# Filter.net
KiCad netlist of a schematic drawn in Altium Designer
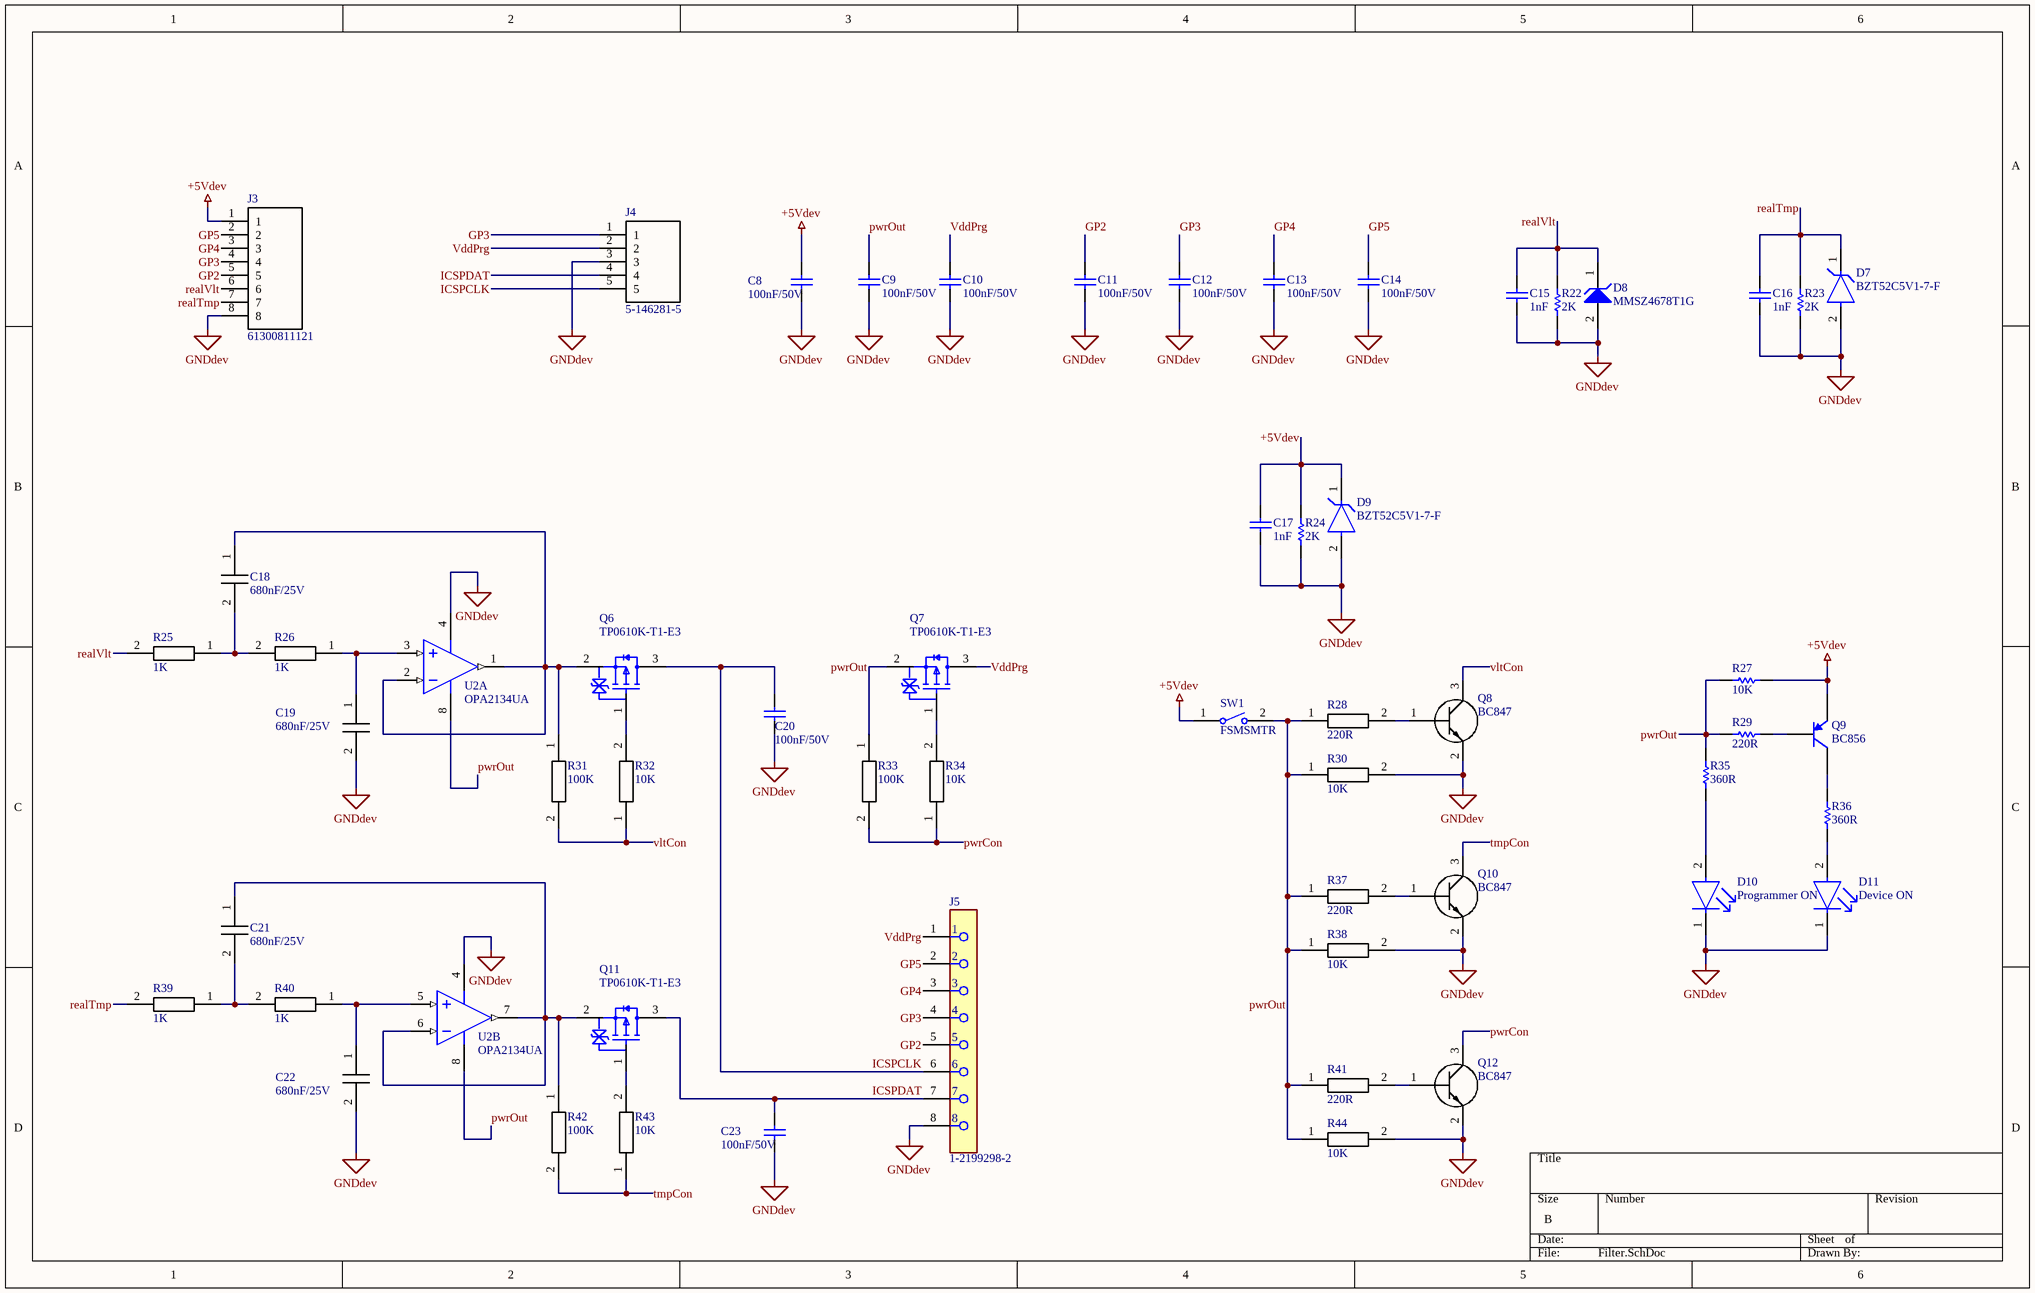
[diagram p0: Filter.SchDoc]

(export (version "E")
  (design (tool "Eeschema 10.0.6"))
  (components
    (comp (ref "C8")
      (value "100nF/50V")
      (footprint "CAPC2013X145X48NL20T23")
      (fields (field (name "MANUFACTURER") "Vitramon") (field (name "PART NUMBER") "VJ0805Y104KNAAT"))
      (libsource (lib "Altium Content Vault") (part "CAP"))
    )
    (comp (ref "C9")
      (value "100nF/50V")
      (footprint "CAPC2013X145X48NL20T23")
      (fields (field (name "MANUFACTURER") "Vitramon") (field (name "PART NUMBER") "VJ0805Y104KNAAT"))
      (libsource (lib "Altium Content Vault") (part "CAP"))
    )
    (comp (ref "C10")
      (value "100nF/50V")
      (footprint "CAPC2013X145X48NL20T23")
      (fields (field (name "MANUFACTURER") "Vitramon") (field (name "PART NUMBER") "VJ0805Y104KNAAT"))
      (libsource (lib "Altium Content Vault") (part "CAP"))
    )
    (comp (ref "C11")
      (value "100nF/50V")
      (footprint "CAPC2013X145X48NL20T23")
      (fields (field (name "MANUFACTURER") "Vitramon") (field (name "PART NUMBER") "VJ0805Y104KNAAT"))
      (libsource (lib "Altium Content Vault") (part "CAP"))
    )
    (comp (ref "C12")
      (value "100nF/50V")
      (footprint "CAPC2013X145X48NL20T23")
      (fields (field (name "MANUFACTURER") "Vitramon") (field (name "PART NUMBER") "VJ0805Y104KNAAT"))
      (libsource (lib "Altium Content Vault") (part "CAP"))
    )
    (comp (ref "C13")
      (value "100nF/50V")
      (footprint "CAPC2013X145X48NL20T23")
      (fields (field (name "MANUFACTURER") "Vitramon") (field (name "PART NUMBER") "VJ0805Y104KNAAT"))
      (libsource (lib "Altium Content Vault") (part "CAP"))
    )
    (comp (ref "C14")
      (value "100nF/50V")
      (footprint "CAPC2013X145X48NL20T23")
      (fields (field (name "MANUFACTURER") "Vitramon") (field (name "PART NUMBER") "VJ0805Y104KNAAT"))
      (libsource (lib "Altium Content Vault") (part "CAP"))
    )
    (comp (ref "C15")
      (value "1nF")
      (footprint "CAPC2013X145X48ML20T23")
      (fields (field (name "PART NUMBER") "VJ0805Y102KXAMC") (field (name "MANUFACTURER") "Vitramon"))
      (libsource (lib "Altium Content Vault") (part "CAP"))
    )
    (comp (ref "C16")
      (value "1nF")
      (footprint "CAPC2013X145X48ML20T23")
      (fields (field (name "PART NUMBER") "VJ0805Y102KXAMC") (field (name "MANUFACTURER") "Vitramon"))
      (libsource (lib "Altium Content Vault") (part "CAP"))
    )
    (comp (ref "C17")
      (value "1nF")
      (footprint "CAPC2013X145X48ML20T23")
      (fields (field (name "PART NUMBER") "VJ0805Y102KXAMC") (field (name "MANUFACTURER") "Vitramon"))
      (libsource (lib "Altium Content Vault") (part "CAP"))
    )
    (comp (ref "C18")
      (value "680nF/25V")
      (footprint "SamacSys:CAPC2012X95N")
      (description "Capacitor")
      (fields (field (name "MANUFACTURER_PART_NUMBER") "GRM219B31E684KA88D"))
      (libsource (lib "*") (part "GRM219B31E684KA88D"))
    )
    (comp (ref "C19")
      (value "680nF/25V")
      (footprint "SamacSys:CAPC2012X95N")
      (description "Capacitor")
      (fields (field (name "MANUFACTURER_PART_NUMBER") "GRM219B31E684KA88D"))
      (libsource (lib "*") (part "GRM219B31E684KA88D"))
    )
    (comp (ref "C20")
      (value "100nF/50V")
      (footprint "CAPC2013X145X48NL20T23")
      (fields (field (name "MANUFACTURER") "Vitramon") (field (name "PART NUMBER") "VJ0805Y104KNAAT"))
      (libsource (lib "Altium Content Vault") (part "CAP"))
    )
    (comp (ref "C21")
      (value "680nF/25V")
      (footprint "SamacSys:CAPC2012X95N")
      (description "Capacitor")
      (fields (field (name "MANUFACTURER_PART_NUMBER") "GRM219B31E684KA88D"))
      (libsource (lib "*") (part "GRM219B31E684KA88D"))
    )
    (comp (ref "C22")
      (value "680nF/25V")
      (footprint "SamacSys:CAPC2012X95N")
      (description "Capacitor")
      (fields (field (name "MANUFACTURER_PART_NUMBER") "GRM219B31E684KA88D"))
      (libsource (lib "*") (part "GRM219B31E684KA88D"))
    )
    (comp (ref "C23")
      (value "100nF/50V")
      (footprint "CAPC2013X145X48NL20T23")
      (fields (field (name "MANUFACTURER") "Vitramon") (field (name "PART NUMBER") "VJ0805Y104KNAAT"))
      (libsource (lib "Altium Content Vault") (part "CAP"))
    )
    (comp (ref "D7")
      (value "BZT52C5V1-7-F")
      (footprint "FP-SOD123-MFG")
      (description "DIODE ZENER 5.1V 500MW SOD123")
      (fields
        (field (name "OCTOPART") "https://octopart.com/bzt52c5v1-7-f-diodes+inc.-326718")
        (field (name "MANUFACTURER") "Diodes Incorporated")
      )
      (libsource (lib "Altium Content Vault") (part "f813f71cba58e380607f5dd3caf9714"))
    )
    (comp (ref "D8")
      (value "MMSZ4678T1G")
      (footprint "ONSC-SOD-123-2-425-04_V")
      (description "Zener Voltage Regulator, 500 mW, 2-Pin SOD-123, Pb-Free, Tape and Reel")
      (fields (field (name "MANUFACTURER") "On Semiconductor"))
      (libsource (lib "Altium Content Vault") (part "ONSC-K1A2-2"))
    )
    (comp (ref "D9")
      (value "BZT52C5V1-7-F")
      (footprint "FP-SOD123-MFG")
      (description "DIODE ZENER 5.1V 500MW SOD123")
      (fields
        (field (name "OCTOPART") "https://octopart.com/bzt52c5v1-7-f-diodes+inc.-326718")
        (field (name "MANUFACTURER") "Diodes Incorporated")
      )
      (libsource (lib "Altium Content Vault") (part "f813f71cba58e380607f5dd3caf9714"))
    )
    (comp (ref "D10")
      (value "Programmer ON")
      (footprint "FP-LG_R971-MFG")
      (description "LED GREEN DIFFUSED 0805 SMD")
      (libsource (lib "Altium Content Vault") (part "8706943c75ba83719d021d2fdc84c58"))
    )
    (comp (ref "D11")
      (value "Device ON")
      (footprint "FP-LS_R976-MFG")
      (description "LED RED DIFFUSED 0805 SMD")
      (libsource (lib "Altium Content Vault") (part "8706943c75ba83719d021d2fdc84c58"))
    )
    (comp (ref "J3")
      (value "61300811121")
      (footprint "SamacSys:HDRV8W64P0X254_1X8_2032X254X854P")
      (description "Connector")
      (fields (field (name "MOUSER PART NUMBER") "710-61300811121"))
      (libsource (lib "*") (part "61300811121"))
    )
    (comp (ref "J4")
      (value "5-146281-5")
      (footprint "SamacSys:HDRV5W67P0X254_1X5_1229X234X821P")
      (description "Connector")
      (fields (field (name "MOUSER PART NUMBER") "571-5-146281-5"))
      (libsource (lib "*") (part "5-146281-5"))
    )
    (comp (ref "J5")
      (value "1-2199298-2")
      (footprint "FP-1-2199298-2-MFG")
      (description "CONN IC DIP SOCKET 8POS TIN")
      (libsource (lib "Altium Content Vault") (part "b0a0b555dd3abf3683e7c330df25cc4"))
    )
    (comp (ref "Q6")
      (value "TP0610K-T1-E3")
      (footprint "FP-S-03946-MFG")
      (description "MOSFET P-CH 60V 185MA SOT23-3")
      (fields
        (field (name "MANUFACTURER") "Vishay")
        (field (name "OCTOPART") "https://octopart.com/tp0610k-t1-e3-vishay-40944172")
      )
      (libsource (lib "Altium Content Vault") (part "bc9d61678d3f6143cc1ffb3a369bd6c"))
    )
    (comp (ref "Q7")
      (value "TP0610K-T1-E3")
      (footprint "FP-S-03946-MFG")
      (description "MOSFET P-CH 60V 185MA SOT23-3")
      (fields
        (field (name "MANUFACTURER") "Vishay")
        (field (name "OCTOPART") "https://octopart.com/tp0610k-t1-e3-vishay-40944172")
      )
      (libsource (lib "Altium Content Vault") (part "bc9d61678d3f6143cc1ffb3a369bd6c"))
    )
    (comp (ref "Q8")
      (value "BC847")
      (footprint "SamacSys:BC847215")
      (description "Transistor BJT NPN")
      (fields
        (field (name "MANUFACTURER_PART_NUMBER") "BC847,215")
        (field (name "MOUSER PART NUMBER") "771-BC847215")
      )
      (libsource (lib "*") (part "BC847,215"))
    )
    (comp (ref "Q9")
      (value "BC856")
      (footprint "NXP-SOT23-3_V")
      (description "PNP General Purpose Transistor, 65 V, -65 to 150 degC, 3-Pin SOT23, RoHS")
      (fields (field (name "MANUFACTURER") "NXP"))
      (libsource (lib "Altium Content Vault") (part "BJT-PNP-BEC-3"))
    )
    (comp (ref "Q10")
      (value "BC847")
      (footprint "SamacSys:BC847215")
      (description "Transistor BJT NPN")
      (fields
        (field (name "MANUFACTURER_PART_NUMBER") "BC847,215")
        (field (name "MOUSER PART NUMBER") "771-BC847215")
      )
      (libsource (lib "*") (part "BC847,215"))
    )
    (comp (ref "Q11")
      (value "TP0610K-T1-E3")
      (footprint "FP-S-03946-MFG")
      (description "MOSFET P-CH 60V 185MA SOT23-3")
      (fields
        (field (name "MANUFACTURER") "Vishay")
        (field (name "OCTOPART") "https://octopart.com/tp0610k-t1-e3-vishay-40944172")
      )
      (libsource (lib "Altium Content Vault") (part "bc9d61678d3f6143cc1ffb3a369bd6c"))
    )
    (comp (ref "Q12")
      (value "BC847")
      (footprint "SamacSys:BC847215")
      (description "Transistor BJT NPN")
      (fields
        (field (name "MANUFACTURER_PART_NUMBER") "BC847,215")
        (field (name "MOUSER PART NUMBER") "771-BC847215")
      )
      (libsource (lib "*") (part "BC847,215"))
    )
    (comp (ref "R22")
      (value "2K")
      (footprint "RESC2013X55X40NL15T20")
      (fields (field (name "MANUFACTURER") "Vishay Dale") (field (name "PART NUMBER") "TNPW08052K00BEEN"))
      (libsource (lib "Altium Content Vault") (part "RES"))
    )
    (comp (ref "R23")
      (value "2K")
      (footprint "RESC2013X55X40NL15T20")
      (fields (field (name "MANUFACTURER") "Vishay Dale") (field (name "PART NUMBER") "TNPW08052K00BEEN"))
      (libsource (lib "Altium Content Vault") (part "RES"))
    )
    (comp (ref "R24")
      (value "2K")
      (footprint "RESC2013X55X40NL15T20")
      (fields (field (name "MANUFACTURER") "Vishay Dale") (field (name "PART NUMBER") "TNPW08052K00BEEN"))
      (libsource (lib "Altium Content Vault") (part "RES"))
    )
    (comp (ref "R25")
      (value "1K")
      (footprint "SamacSys:RESC2012X65N")
      (description "Resistor")
      (fields
        (field (name "MANUFACTURER_PART_NUMBER") "CPF0805B360RE1")
        (field (name "MOUSER PART NUMBER") "279-CPF0805B360RE1")
      )
      (libsource (lib "*") (part "CPF0805B360RE1"))
    )
    (comp (ref "R26")
      (value "1K")
      (footprint "SamacSys:RESC2012X65N")
      (description "Resistor")
      (fields
        (field (name "MANUFACTURER_PART_NUMBER") "CPF0805B360RE1")
        (field (name "MOUSER PART NUMBER") "279-CPF0805B360RE1")
      )
      (libsource (lib "*") (part "CPF0805B360RE1"))
    )
    (comp (ref "R27")
      (value "10K")
      (footprint "RESC2013X55X40NL15T20")
      (fields (field (name "MANUFACTURER") "Vishay Dale") (field (name "PART NUMBER") "TNPW08052K00BEEN"))
      (libsource (lib "Altium Content Vault") (part "RES"))
    )
    (comp (ref "R28")
      (value "220R")
      (footprint "SamacSys:RESC2012X65N")
      (description "Resistor")
      (fields (field (name "MANUFACTURER_PART_NUMBER") "CPF0805B220RE"))
      (libsource (lib "*") (part "CPF0805B220RE"))
    )
    (comp (ref "R29")
      (value "220R")
      (footprint "RESC2013X55X40NL15T20")
      (fields (field (name "MANUFACTURER") "Vishay Dale") (field (name "PART NUMBER") "TNPW08052K00BEEN"))
      (libsource (lib "Altium Content Vault") (part "RES"))
    )
    (comp (ref "R30")
      (value "10K")
      (footprint "SamacSys:RESC2012X65N")
      (description "Resistor")
      (fields (field (name "MANUFACTURER_PART_NUMBER") "CPF0805B220RE"))
      (libsource (lib "*") (part "CPF0805B220RE"))
    )
    (comp (ref "R31")
      (value "100K")
      (footprint "SamacSys:RESC2012X65N")
      (description "Resistor")
      (fields
        (field (name "MANUFACTURER_PART_NUMBER") "CPF0805B360RE1")
        (field (name "MOUSER PART NUMBER") "279-CPF0805B360RE1")
      )
      (libsource (lib "*") (part "CPF0805B360RE1"))
    )
    (comp (ref "R32")
      (value "10K")
      (footprint "SamacSys:RESC2012X65N")
      (description "Resistor")
      (fields
        (field (name "MANUFACTURER_PART_NUMBER") "CPF0805B360RE1")
        (field (name "MOUSER PART NUMBER") "279-CPF0805B360RE1")
      )
      (libsource (lib "*") (part "CPF0805B360RE1"))
    )
    (comp (ref "R33")
      (value "100K")
      (footprint "SamacSys:RESC2012X65N")
      (description "Resistor")
      (fields
        (field (name "MANUFACTURER_PART_NUMBER") "CPF0805B360RE1")
        (field (name "MOUSER PART NUMBER") "279-CPF0805B360RE1")
      )
      (libsource (lib "*") (part "CPF0805B360RE1"))
    )
    (comp (ref "R34")
      (value "10K")
      (footprint "SamacSys:RESC2012X65N")
      (description "Resistor")
      (fields
        (field (name "MANUFACTURER_PART_NUMBER") "CPF0805B360RE1")
        (field (name "MOUSER PART NUMBER") "279-CPF0805B360RE1")
      )
      (libsource (lib "*") (part "CPF0805B360RE1"))
    )
    (comp (ref "R35")
      (value "360R")
      (footprint "RESC2013X55X40NL15T20")
      (fields (field (name "MANUFACTURER") "Vishay Dale") (field (name "PART NUMBER") "TNPW08052K00BEEN"))
      (libsource (lib "Altium Content Vault") (part "RES"))
    )
    (comp (ref "R36")
      (value "360R")
      (footprint "RESC2013X55X40NL15T20")
      (fields (field (name "MANUFACTURER") "Vishay Dale") (field (name "PART NUMBER") "TNPW08052K00BEEN"))
      (libsource (lib "Altium Content Vault") (part "RES"))
    )
    (comp (ref "R37")
      (value "220R")
      (footprint "SamacSys:RESC2012X65N")
      (description "Resistor")
      (fields (field (name "MANUFACTURER_PART_NUMBER") "CPF0805B220RE"))
      (libsource (lib "*") (part "CPF0805B220RE"))
    )
    (comp (ref "R38")
      (value "10K")
      (footprint "SamacSys:RESC2012X65N")
      (description "Resistor")
      (fields (field (name "MANUFACTURER_PART_NUMBER") "CPF0805B220RE"))
      (libsource (lib "*") (part "CPF0805B220RE"))
    )
    (comp (ref "R39")
      (value "1K")
      (footprint "SamacSys:RESC2012X65N")
      (description "Resistor")
      (fields
        (field (name "MANUFACTURER_PART_NUMBER") "CPF0805B360RE1")
        (field (name "MOUSER PART NUMBER") "279-CPF0805B360RE1")
      )
      (libsource (lib "*") (part "CPF0805B360RE1"))
    )
    (comp (ref "R40")
      (value "1K")
      (footprint "SamacSys:RESC2012X65N")
      (description "Resistor")
      (fields
        (field (name "MANUFACTURER_PART_NUMBER") "CPF0805B360RE1")
        (field (name "MOUSER PART NUMBER") "279-CPF0805B360RE1")
      )
      (libsource (lib "*") (part "CPF0805B360RE1"))
    )
    (comp (ref "R41")
      (value "220R")
      (footprint "SamacSys:RESC2012X65N")
      (description "Resistor")
      (fields (field (name "MANUFACTURER_PART_NUMBER") "CPF0805B220RE"))
      (libsource (lib "*") (part "CPF0805B220RE"))
    )
    (comp (ref "R42")
      (value "100K")
      (footprint "SamacSys:RESC2012X65N")
      (description "Resistor")
      (fields
        (field (name "MANUFACTURER_PART_NUMBER") "CPF0805B360RE1")
        (field (name "MOUSER PART NUMBER") "279-CPF0805B360RE1")
      )
      (libsource (lib "*") (part "CPF0805B360RE1"))
    )
    (comp (ref "R43")
      (value "10K")
      (footprint "SamacSys:RESC2012X65N")
      (description "Resistor")
      (fields
        (field (name "MANUFACTURER_PART_NUMBER") "CPF0805B360RE1")
        (field (name "MOUSER PART NUMBER") "279-CPF0805B360RE1")
      )
      (libsource (lib "*") (part "CPF0805B360RE1"))
    )
    (comp (ref "R44")
      (value "10K")
      (footprint "SamacSys:RESC2012X65N")
      (description "Resistor")
      (fields (field (name "MANUFACTURER_PART_NUMBER") "CPF0805B220RE"))
      (libsource (lib "*") (part "CPF0805B220RE"))
    )
    (comp (ref "SW1")
      (value "FSMSMTR")
      (footprint "TECO-FSMSMTR_V")
      (description "FSMSM Push Button Switch, 50 mA, -35 to 85 degC, 2-Pin SMD, RoHS, Tape and Reel")
      (fields (field (name "MANUFACTURER") "TE Connectivity"))
      (libsource (lib "Altium Content Vault") (part "SW-SPST-2_C"))
    )
    (comp (ref "U2")
      (value "OPA2134UA")
      (footprint "D0008A_L")
      (fields (field (name "MANUFACTURER") "Texas Instruments"))
      (libsource (lib "Altium Content Vault") (part "TI-OPA2134D8"))
    )
  )
  (nets
    (net (code "1") (name "+5Vdev") (class "Default")
      (node (ref "C17") (pin "2") (pinfunction "2_2") (pintype "passive"))
      (node (ref "C8") (pin "2") (pinfunction "2_2") (pintype "passive"))
      (node (ref "D9") (pin "1") (pinfunction "C_1") (pintype "passive"))
      (node (ref "J3") (pin "1") (pinfunction "1_1") (pintype "passive"))
      (node (ref "Q9") (pin "2") (pinfunction "E_2") (pintype "passive"))
      (node (ref "R24") (pin "2") (pinfunction "2_2") (pintype "passive"))
      (node (ref "R27") (pin "1") (pinfunction "1_1") (pintype "passive"))
      (node (ref "SW1") (pin "1") (pinfunction "1_1") (pintype "passive"))
    )
    (net (code "2") (name "/GP2") (class "Default")
      (node (ref "C11") (pin "1") (pinfunction "1_1") (pintype "passive"))
      (node (ref "J3") (pin "5") (pinfunction "5_5") (pintype "passive"))
      (node (ref "J5") (pin "5") (pinfunction "5_5") (pintype "passive"))
    )
    (net (code "3") (name "/GP3") (class "Default")
      (node (ref "C12") (pin "1") (pinfunction "1_1") (pintype "passive"))
      (node (ref "J3") (pin "4") (pinfunction "4_4") (pintype "passive"))
      (node (ref "J4") (pin "1") (pinfunction "1_1") (pintype "passive"))
      (node (ref "J5") (pin "4") (pinfunction "4_4") (pintype "passive"))
    )
    (net (code "4") (name "/GP4") (class "Default")
      (node (ref "C13") (pin "1") (pinfunction "1_1") (pintype "passive"))
      (node (ref "J3") (pin "3") (pinfunction "3_3") (pintype "passive"))
      (node (ref "J5") (pin "3") (pinfunction "3_3") (pintype "passive"))
    )
    (net (code "5") (name "/GP5") (class "Default")
      (node (ref "C14") (pin "1") (pinfunction "1_1") (pintype "passive"))
      (node (ref "J3") (pin "2") (pinfunction "2_2") (pintype "passive"))
      (node (ref "J5") (pin "2") (pinfunction "2_2") (pintype "passive"))
    )
    (net (code "6") (name "/ICSPCLK") (class "Default")
      (node (ref "C20") (pin "2") (pinfunction "2_2") (pintype "passive"))
      (node (ref "J4") (pin "5") (pinfunction "5_5") (pintype "passive"))
      (node (ref "J5") (pin "6") (pinfunction "6_6") (pintype "passive"))
      (node (ref "Q6") (pin "3") (pinfunction "D_3") (pintype "passive"))
    )
    (net (code "7") (name "/ICSPDAT") (class "Default")
      (node (ref "C23") (pin "2") (pinfunction "2_2") (pintype "passive"))
      (node (ref "J4") (pin "4") (pinfunction "4_4") (pintype "passive"))
      (node (ref "J5") (pin "7") (pinfunction "7_7") (pintype "passive"))
      (node (ref "Q11") (pin "3") (pinfunction "D_3") (pintype "passive"))
    )
    (net (code "8") (name "/VddPrg") (class "Default")
      (node (ref "C10") (pin "1") (pinfunction "1_1") (pintype "passive"))
      (node (ref "J4") (pin "2") (pinfunction "2_2") (pintype "passive"))
      (node (ref "J5") (pin "1") (pinfunction "1_1") (pintype "passive"))
      (node (ref "Q7") (pin "3") (pinfunction "D_3") (pintype "passive"))
    )
    (net (code "9") (name "/pwrCon") (class "Default")
      (node (ref "Q12") (pin "3") (pinfunction "C_3") (pintype "passive"))
      (node (ref "R33") (pin "2") (pinfunction "2_2") (pintype "passive"))
      (node (ref "R34") (pin "1") (pinfunction "1_1") (pintype "passive"))
    )
    (net (code "10") (name "/pwrOut") (class "Default")
      (node (ref "C9") (pin "1") (pinfunction "1_1") (pintype "passive"))
      (node (ref "Q7") (pin "2") (pinfunction "S_2") (pintype "passive"))
      (node (ref "R27") (pin "2") (pinfunction "2_2") (pintype "passive"))
      (node (ref "R28") (pin "1") (pinfunction "1_1") (pintype "passive"))
      (node (ref "R29") (pin "2") (pinfunction "2_2") (pintype "passive"))
      (node (ref "R30") (pin "1") (pinfunction "1_1") (pintype "passive"))
      (node (ref "R33") (pin "1") (pinfunction "1_1") (pintype "passive"))
      (node (ref "R35") (pin "2") (pinfunction "2_2") (pintype "passive"))
      (node (ref "R37") (pin "1") (pinfunction "1_1") (pintype "passive"))
      (node (ref "R38") (pin "1") (pinfunction "1_1") (pintype "passive"))
      (node (ref "R41") (pin "1") (pinfunction "1_1") (pintype "passive"))
      (node (ref "R44") (pin "1") (pinfunction "1_1") (pintype "passive"))
      (node (ref "SW1") (pin "2") (pinfunction "2_2") (pintype "passive"))
      (node (ref "U2") (pin "8") (pinfunction "V+_8") (pintype "power_in"))
    )
    (net (code "11") (name "/realTmp") (class "Default")
      (node (ref "C16") (pin "2") (pinfunction "2_2") (pintype "passive"))
      (node (ref "D7") (pin "1") (pinfunction "C_1") (pintype "passive"))
      (node (ref "J3") (pin "7") (pinfunction "7_7") (pintype "passive"))
      (node (ref "R23") (pin "2") (pinfunction "2_2") (pintype "passive"))
      (node (ref "R39") (pin "2") (pinfunction "2_2") (pintype "passive"))
    )
    (net (code "12") (name "/realVlt") (class "Default")
      (node (ref "C15") (pin "2") (pinfunction "2_2") (pintype "passive"))
      (node (ref "D8") (pin "1") (pinfunction "K_1") (pintype "passive"))
      (node (ref "J3") (pin "6") (pinfunction "6_6") (pintype "passive"))
      (node (ref "R22") (pin "2") (pinfunction "2_2") (pintype "passive"))
      (node (ref "R25") (pin "2") (pinfunction "2_2") (pintype "passive"))
    )
    (net (code "13") (name "/tmpCon") (class "Default")
      (node (ref "Q10") (pin "3") (pinfunction "C_3") (pintype "passive"))
      (node (ref "R42") (pin "2") (pinfunction "2_2") (pintype "passive"))
      (node (ref "R43") (pin "1") (pinfunction "1_1") (pintype "passive"))
    )
    (net (code "14") (name "/vltCon") (class "Default")
      (node (ref "Q8") (pin "3") (pinfunction "C_3") (pintype "passive"))
      (node (ref "R31") (pin "2") (pinfunction "2_2") (pintype "passive"))
      (node (ref "R32") (pin "1") (pinfunction "1_1") (pintype "passive"))
    )
    (net (code "15") (name "GNDdev") (class "Default")
      (node (ref "C10") (pin "2") (pinfunction "2_2") (pintype "passive"))
      (node (ref "C11") (pin "2") (pinfunction "2_2") (pintype "passive"))
      (node (ref "C12") (pin "2") (pinfunction "2_2") (pintype "passive"))
      (node (ref "C13") (pin "2") (pinfunction "2_2") (pintype "passive"))
      (node (ref "C14") (pin "2") (pinfunction "2_2") (pintype "passive"))
      (node (ref "C15") (pin "1") (pinfunction "1_1") (pintype "passive"))
      (node (ref "C16") (pin "1") (pinfunction "1_1") (pintype "passive"))
      (node (ref "C17") (pin "1") (pinfunction "1_1") (pintype "passive"))
      (node (ref "C19") (pin "2") (pinfunction "2_2") (pintype "passive"))
      (node (ref "C20") (pin "1") (pinfunction "1_1") (pintype "passive"))
      (node (ref "C22") (pin "2") (pinfunction "2_2") (pintype "passive"))
      (node (ref "C23") (pin "1") (pinfunction "1_1") (pintype "passive"))
      (node (ref "C8") (pin "1") (pinfunction "1_1") (pintype "passive"))
      (node (ref "C9") (pin "2") (pinfunction "2_2") (pintype "passive"))
      (node (ref "D10") (pin "1") (pinfunction "C_1") (pintype "passive"))
      (node (ref "D11") (pin "1") (pinfunction "C_1") (pintype "passive"))
      (node (ref "D7") (pin "2") (pinfunction "A_2") (pintype "passive"))
      (node (ref "D8") (pin "2") (pinfunction "A_2") (pintype "passive"))
      (node (ref "D9") (pin "2") (pinfunction "A_2") (pintype "passive"))
      (node (ref "J3") (pin "8") (pinfunction "8_8") (pintype "passive"))
      (node (ref "J4") (pin "3") (pinfunction "3_3") (pintype "passive"))
      (node (ref "J5") (pin "8") (pinfunction "8_8") (pintype "passive"))
      (node (ref "Q10") (pin "2") (pinfunction "E_2") (pintype "passive"))
      (node (ref "Q12") (pin "2") (pinfunction "E_2") (pintype "passive"))
      (node (ref "Q8") (pin "2") (pinfunction "E_2") (pintype "passive"))
      (node (ref "R22") (pin "1") (pinfunction "1_1") (pintype "passive"))
      (node (ref "R23") (pin "1") (pinfunction "1_1") (pintype "passive"))
      (node (ref "R24") (pin "1") (pinfunction "1_1") (pintype "passive"))
      (node (ref "R30") (pin "2") (pinfunction "2_2") (pintype "passive"))
      (node (ref "R38") (pin "2") (pinfunction "2_2") (pintype "passive"))
      (node (ref "R44") (pin "2") (pinfunction "2_2") (pintype "passive"))
      (node (ref "U2") (pin "4") (pinfunction "V-_4") (pintype "power_in"))
    )
    (net (code "16") (name "Net-(C18-Pad2)") (class "Default")
      (node (ref "C18") (pin "2") (pinfunction "2_2") (pintype "passive"))
      (node (ref "R25") (pin "1") (pinfunction "1_1") (pintype "passive"))
      (node (ref "R26") (pin "2") (pinfunction "2_2") (pintype "passive"))
    )
    (net (code "17") (name "Net-(C21-Pad2)") (class "Default")
      (node (ref "C21") (pin "2") (pinfunction "2_2") (pintype "passive"))
      (node (ref "R39") (pin "1") (pinfunction "1_1") (pintype "passive"))
      (node (ref "R40") (pin "2") (pinfunction "2_2") (pintype "passive"))
    )
    (net (code "18") (name "Net-(D10-A)") (class "Default")
      (node (ref "D10") (pin "2") (pinfunction "A_2") (pintype "passive"))
      (node (ref "R35") (pin "1") (pinfunction "1_1") (pintype "passive"))
    )
    (net (code "19") (name "Net-(D11-A)") (class "Default")
      (node (ref "D11") (pin "2") (pinfunction "A_2") (pintype "passive"))
      (node (ref "R36") (pin "1") (pinfunction "1_1") (pintype "passive"))
    )
    (net (code "20") (name "Net-(Q6-G)") (class "Default")
      (node (ref "Q6") (pin "1") (pinfunction "G_1") (pintype "passive"))
      (node (ref "R32") (pin "2") (pinfunction "2_2") (pintype "passive"))
    )
    (net (code "21") (name "Net-(Q6-S)") (class "Default")
      (node (ref "C18") (pin "1") (pinfunction "1_1") (pintype "passive"))
      (node (ref "Q6") (pin "2") (pinfunction "S_2") (pintype "passive"))
      (node (ref "R31") (pin "1") (pinfunction "1_1") (pintype "passive"))
      (node (ref "U2") (pin "1") (pinfunction "OUT_A_1") (pintype "output"))
      (node (ref "U2") (pin "2") (pinfunction "IN_A-_2") (pintype "input"))
    )
    (net (code "22") (name "Net-(Q7-G)") (class "Default")
      (node (ref "Q7") (pin "1") (pinfunction "G_1") (pintype "passive"))
      (node (ref "R34") (pin "2") (pinfunction "2_2") (pintype "passive"))
    )
    (net (code "23") (name "Net-(Q8-B)") (class "Default")
      (node (ref "Q8") (pin "1") (pinfunction "B_1") (pintype "passive"))
      (node (ref "R28") (pin "2") (pinfunction "2_2") (pintype "passive"))
    )
    (net (code "24") (name "Net-(Q9-B)") (class "Default")
      (node (ref "Q9") (pin "1") (pinfunction "B_1") (pintype "passive"))
      (node (ref "R29") (pin "1") (pinfunction "1_1") (pintype "passive"))
    )
    (net (code "25") (name "Net-(Q9-C)") (class "Default")
      (node (ref "Q9") (pin "3") (pinfunction "C_3") (pintype "passive"))
      (node (ref "R36") (pin "2") (pinfunction "2_2") (pintype "passive"))
    )
    (net (code "26") (name "Net-(Q10-B)") (class "Default")
      (node (ref "Q10") (pin "1") (pinfunction "B_1") (pintype "passive"))
      (node (ref "R37") (pin "2") (pinfunction "2_2") (pintype "passive"))
    )
    (net (code "27") (name "Net-(Q11-G)") (class "Default")
      (node (ref "Q11") (pin "1") (pinfunction "G_1") (pintype "passive"))
      (node (ref "R43") (pin "2") (pinfunction "2_2") (pintype "passive"))
    )
    (net (code "28") (name "Net-(Q11-S)") (class "Default")
      (node (ref "C21") (pin "1") (pinfunction "1_1") (pintype "passive"))
      (node (ref "Q11") (pin "2") (pinfunction "S_2") (pintype "passive"))
      (node (ref "R42") (pin "1") (pinfunction "1_1") (pintype "passive"))
      (node (ref "U2") (pin "6") (pinfunction "IN_B-_6") (pintype "input"))
      (node (ref "U2") (pin "7") (pinfunction "OUT_B_7") (pintype "output"))
    )
    (net (code "29") (name "Net-(Q12-B)") (class "Default")
      (node (ref "Q12") (pin "1") (pinfunction "B_1") (pintype "passive"))
      (node (ref "R41") (pin "2") (pinfunction "2_2") (pintype "passive"))
    )
    (net (code "30") (name "Net-(U2A-IN_A+)") (class "Default")
      (node (ref "C19") (pin "1") (pinfunction "1_1") (pintype "passive"))
      (node (ref "R26") (pin "1") (pinfunction "1_1") (pintype "passive"))
      (node (ref "U2") (pin "3") (pinfunction "IN_A+_3") (pintype "input"))
    )
    (net (code "31") (name "Net-(U2B-IN_B+)") (class "Default")
      (node (ref "C22") (pin "1") (pinfunction "1_1") (pintype "passive"))
      (node (ref "R40") (pin "1") (pinfunction "1_1") (pintype "passive"))
      (node (ref "U2") (pin "5") (pinfunction "IN_B+_5") (pintype "input"))
    )
  )
)
